# MCU.net
KiCad netlist of a schematic drawn in Altium Designer
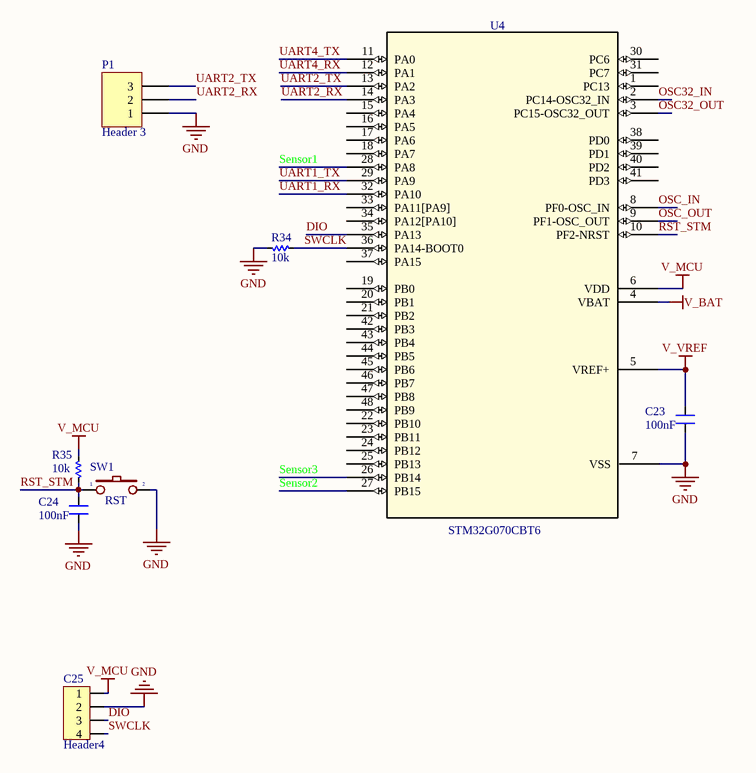
[diagram p0: MCU.SchDoc]

(export (version "E")
  (design (tool "Eeschema 10.0.6"))
  (components
    (comp (ref "C23") (value "100nF") (footprint "CN-SMD-0603") (libsource (lib "thu vien 3d") (part "CN")))
    (comp (ref "C24") (value "100nF") (footprint "CN-SMD-0603") (libsource (lib "thu vien 3d") (part "CN")))
    (comp (ref "C25")
      (value "Header4")
      (footprint "Header4")
      (description "Header IDC, 4 x 1 Pin Vertical 2.54mm Pitch (Non-Boxed, Male)")
      (fields
        (field (name "MANUFACTURER") "Würth Elektronik eiSos GmbH")
        (field (name "PARTNO") "613002143121")
        (field (name "CREATED BY") "Karrer Zheng")
      )
      (libsource (lib "thu vien 3d") (part "Header4"))
    )
    (comp (ref "P1")
      (value "Header 3")
      (footprint "Header 3")
      (description "Header, 3-Pin")
      (fields (field (name "PUBLISHER") "Altium Limited"))
      (libsource (lib "hphonglib") (part "Header 3"))
    )
    (comp (ref "R34")
      (value "10k")
      (footprint "RES-SMD-0603")
      (description "Resistor")
      (fields
        (field (name "MANUFACTURER") "Generic Components")
        (field (name "PUBLISHER") "Altium Hobart Technology Centre")
      )
      (libsource (lib "thu vien 3d") (part "Res-SMD"))
    )
    (comp (ref "R35")
      (value "10k")
      (footprint "RES-SMD-0603")
      (description "Resistor")
      (fields
        (field (name "MANUFACTURER") "Generic Components")
        (field (name "PUBLISHER") "Altium Hobart Technology Centre")
      )
      (libsource (lib "thu vien 3d") (part "Res-SMD"))
    )
    (comp (ref "SW1")
      (value "RST")
      (footprint "SW1-SMD")
      (description "Switch button 2 pin")
      (libsource (lib "thu vien 3d") (part "SW2"))
    )
    (comp (ref "U4")
      (value "STM32G070CBT6")
      (footprint "STM32G070CBT6")
      (description "No Description Available")
      (fields (field (name "COPYRIGHT") "Copyright (C) 2018 Accelerated Designs. All rights reserved"))
      (libsource (lib "Nichietsuvn") (part "STM32G070CBT6"))
    )
  )
  (nets
    (net (code "1") (name "/DIO") (class "Default")
      (node (ref "C25") (pin "3") (pinfunction "3_3") (pintype "passive"))
      (node (ref "U4") (pin "35") (pinfunction "PA13_35") (pintype "bidirectional"))
    )
    (net (code "2") (name "/OSC32_IN") (class "Default")
      (node (ref "U4") (pin "2") (pinfunction "PC14-OSC32_IN_2") (pintype "bidirectional"))
    )
    (net (code "3") (name "/OSC32_OUT") (class "Default")
      (node (ref "U4") (pin "3") (pinfunction "PC15-OSC32_OUT_3") (pintype "bidirectional"))
    )
    (net (code "4") (name "/OSC_IN") (class "Default")
      (node (ref "U4") (pin "8") (pinfunction "PF0-OSC_IN_8") (pintype "bidirectional"))
    )
    (net (code "5") (name "/OSC_OUT") (class "Default")
      (node (ref "U4") (pin "9") (pinfunction "PF1-OSC_OUT_9") (pintype "bidirectional"))
    )
    (net (code "6") (name "/RST_STM") (class "Default")
      (node (ref "C24") (pin "1") (pinfunction "1_1") (pintype "passive"))
      (node (ref "R35") (pin "2") (pinfunction "2_2") (pintype "passive"))
      (node (ref "SW1") (pin "1") (pinfunction "1_1") (pintype "passive"))
      (node (ref "U4") (pin "10") (pinfunction "PF2-NRST_10") (pintype "bidirectional"))
    )
    (net (code "7") (name "/SWCLK") (class "Default")
      (node (ref "C25") (pin "4") (pinfunction "4_4") (pintype "passive"))
      (node (ref "R34") (pin "1") (pinfunction "1_1") (pintype "passive"))
      (node (ref "U4") (pin "36") (pinfunction "PA14-BOOT0_36") (pintype "bidirectional"))
    )
    (net (code "8") (name "/Sensor1") (class "Default")
      (node (ref "U4") (pin "28") (pinfunction "PA8_28") (pintype "bidirectional"))
    )
    (net (code "9") (name "/Sensor2") (class "Default")
      (node (ref "U4") (pin "27") (pinfunction "PB15_27") (pintype "bidirectional"))
    )
    (net (code "10") (name "/Sensor3") (class "Default")
      (node (ref "U4") (pin "26") (pinfunction "PB14_26") (pintype "bidirectional"))
    )
    (net (code "11") (name "/UART1_RX") (class "Default")
      (node (ref "U4") (pin "32") (pinfunction "PA10_32") (pintype "bidirectional"))
    )
    (net (code "12") (name "/UART1_TX") (class "Default")
      (node (ref "U4") (pin "29") (pinfunction "PA9_29") (pintype "bidirectional"))
    )
    (net (code "13") (name "/UART2_RX") (class "Default")
      (node (ref "P1") (pin "2") (pinfunction "2_2") (pintype "passive"))
      (node (ref "U4") (pin "14") (pinfunction "PA3_14") (pintype "bidirectional"))
    )
    (net (code "14") (name "/UART2_TX") (class "Default")
      (node (ref "P1") (pin "3") (pinfunction "3_3") (pintype "passive"))
      (node (ref "U4") (pin "13") (pinfunction "PA2_13") (pintype "bidirectional"))
    )
    (net (code "15") (name "/UART4_RX") (class "Default")
      (node (ref "U4") (pin "12") (pinfunction "PA1_12") (pintype "bidirectional"))
    )
    (net (code "16") (name "/UART4_TX") (class "Default")
      (node (ref "U4") (pin "11") (pinfunction "PA0_11") (pintype "bidirectional"))
    )
    (net (code "17") (name "GND") (class "Default")
      (node (ref "C23") (pin "2") (pinfunction "2_2") (pintype "passive"))
      (node (ref "C24") (pin "2") (pinfunction "2_2") (pintype "passive"))
      (node (ref "C25") (pin "2") (pinfunction "2_2") (pintype "passive"))
      (node (ref "P1") (pin "1") (pinfunction "1_1") (pintype "passive"))
      (node (ref "R34") (pin "2") (pinfunction "2_2") (pintype "passive"))
      (node (ref "SW1") (pin "2") (pinfunction "2_2") (pintype "passive"))
      (node (ref "U4") (pin "7") (pinfunction "VSS_7") (pintype "power_in"))
    )
    (net (code "18") (name "V_BAT") (class "Default")
      (node (ref "U4") (pin "4") (pinfunction "VBAT_4") (pintype "power_in"))
    )
    (net (code "19") (name "V_MCU") (class "Default")
      (node (ref "C25") (pin "1") (pinfunction "1_1") (pintype "passive"))
      (node (ref "R35") (pin "1") (pinfunction "1_1") (pintype "passive"))
      (node (ref "U4") (pin "6") (pinfunction "VDD_6") (pintype "power_in"))
    )
    (net (code "20") (name "V_VREF") (class "Default")
      (node (ref "C23") (pin "1") (pinfunction "1_1") (pintype "passive"))
      (node (ref "U4") (pin "5") (pinfunction "VREF+_5") (pintype "power_in"))
    )
    (net (code "21") (name "unconnected-(U4-PA4-Pad15)") (class "Default")
      (node (ref "U4") (pin "15") (pinfunction "PA4_15") (pintype "bidirectional"))
    )
    (net (code "22") (name "unconnected-(U4-PA5-Pad16)") (class "Default")
      (node (ref "U4") (pin "16") (pinfunction "PA5_16") (pintype "bidirectional"))
    )
    (net (code "23") (name "unconnected-(U4-PA6-Pad17)") (class "Default")
      (node (ref "U4") (pin "17") (pinfunction "PA6_17") (pintype "bidirectional"))
    )
    (net (code "24") (name "unconnected-(U4-PA7-Pad18)") (class "Default")
      (node (ref "U4") (pin "18") (pinfunction "PA7_18") (pintype "bidirectional"))
    )
    (net (code "25") (name "unconnected-(U4-PA11[PA9]-Pad33)") (class "Default")
      (node (ref "U4") (pin "33") (pinfunction "PA11[PA9]_33") (pintype "bidirectional"))
    )
    (net (code "26") (name "unconnected-(U4-PA12[PA10]-Pad34)") (class "Default")
      (node (ref "U4") (pin "34") (pinfunction "PA12[PA10]_34") (pintype "bidirectional"))
    )
    (net (code "27") (name "unconnected-(U4-PA15-Pad37)") (class "Default")
      (node (ref "U4") (pin "37") (pinfunction "PA15_37") (pintype "bidirectional"))
    )
    (net (code "28") (name "unconnected-(U4-PB0-Pad19)") (class "Default")
      (node (ref "U4") (pin "19") (pinfunction "PB0_19") (pintype "bidirectional"))
    )
    (net (code "29") (name "unconnected-(U4-PB1-Pad20)") (class "Default")
      (node (ref "U4") (pin "20") (pinfunction "PB1_20") (pintype "bidirectional"))
    )
    (net (code "30") (name "unconnected-(U4-PB2-Pad21)") (class "Default")
      (node (ref "U4") (pin "21") (pinfunction "PB2_21") (pintype "bidirectional"))
    )
    (net (code "31") (name "unconnected-(U4-PB3-Pad42)") (class "Default")
      (node (ref "U4") (pin "42") (pinfunction "PB3_42") (pintype "bidirectional"))
    )
    (net (code "32") (name "unconnected-(U4-PB4-Pad43)") (class "Default")
      (node (ref "U4") (pin "43") (pinfunction "PB4_43") (pintype "bidirectional"))
    )
    (net (code "33") (name "unconnected-(U4-PB5-Pad44)") (class "Default")
      (node (ref "U4") (pin "44") (pinfunction "PB5_44") (pintype "bidirectional"))
    )
    (net (code "34") (name "unconnected-(U4-PB6-Pad45)") (class "Default")
      (node (ref "U4") (pin "45") (pinfunction "PB6_45") (pintype "bidirectional"))
    )
    (net (code "35") (name "unconnected-(U4-PB7-Pad46)") (class "Default")
      (node (ref "U4") (pin "46") (pinfunction "PB7_46") (pintype "bidirectional"))
    )
    (net (code "36") (name "unconnected-(U4-PB8-Pad47)") (class "Default")
      (node (ref "U4") (pin "47") (pinfunction "PB8_47") (pintype "bidirectional"))
    )
    (net (code "37") (name "unconnected-(U4-PB9-Pad48)") (class "Default")
      (node (ref "U4") (pin "48") (pinfunction "PB9_48") (pintype "bidirectional"))
    )
    (net (code "38") (name "unconnected-(U4-PB10-Pad22)") (class "Default")
      (node (ref "U4") (pin "22") (pinfunction "PB10_22") (pintype "bidirectional"))
    )
    (net (code "39") (name "unconnected-(U4-PB11-Pad23)") (class "Default")
      (node (ref "U4") (pin "23") (pinfunction "PB11_23") (pintype "bidirectional"))
    )
    (net (code "40") (name "unconnected-(U4-PB12-Pad24)") (class "Default")
      (node (ref "U4") (pin "24") (pinfunction "PB12_24") (pintype "bidirectional"))
    )
    (net (code "41") (name "unconnected-(U4-PB13-Pad25)") (class "Default")
      (node (ref "U4") (pin "25") (pinfunction "PB13_25") (pintype "bidirectional"))
    )
    (net (code "42") (name "unconnected-(U4-PC6-Pad30)") (class "Default")
      (node (ref "U4") (pin "30") (pinfunction "PC6_30") (pintype "bidirectional"))
    )
    (net (code "43") (name "unconnected-(U4-PC7-Pad31)") (class "Default")
      (node (ref "U4") (pin "31") (pinfunction "PC7_31") (pintype "bidirectional"))
    )
    (net (code "44") (name "unconnected-(U4-PC13-Pad1)") (class "Default")
      (node (ref "U4") (pin "1") (pinfunction "PC13_1") (pintype "bidirectional"))
    )
    (net (code "45") (name "unconnected-(U4-PD0-Pad38)") (class "Default")
      (node (ref "U4") (pin "38") (pinfunction "PD0_38") (pintype "bidirectional"))
    )
    (net (code "46") (name "unconnected-(U4-PD1-Pad39)") (class "Default")
      (node (ref "U4") (pin "39") (pinfunction "PD1_39") (pintype "bidirectional"))
    )
    (net (code "47") (name "unconnected-(U4-PD2-Pad40)") (class "Default")
      (node (ref "U4") (pin "40") (pinfunction "PD2_40") (pintype "bidirectional"))
    )
    (net (code "48") (name "unconnected-(U4-PD3-Pad41)") (class "Default")
      (node (ref "U4") (pin "41") (pinfunction "PD3_41") (pintype "bidirectional"))
    )
  )
)
